# Headers.net
KiCad netlist of a schematic drawn in Altium Designer
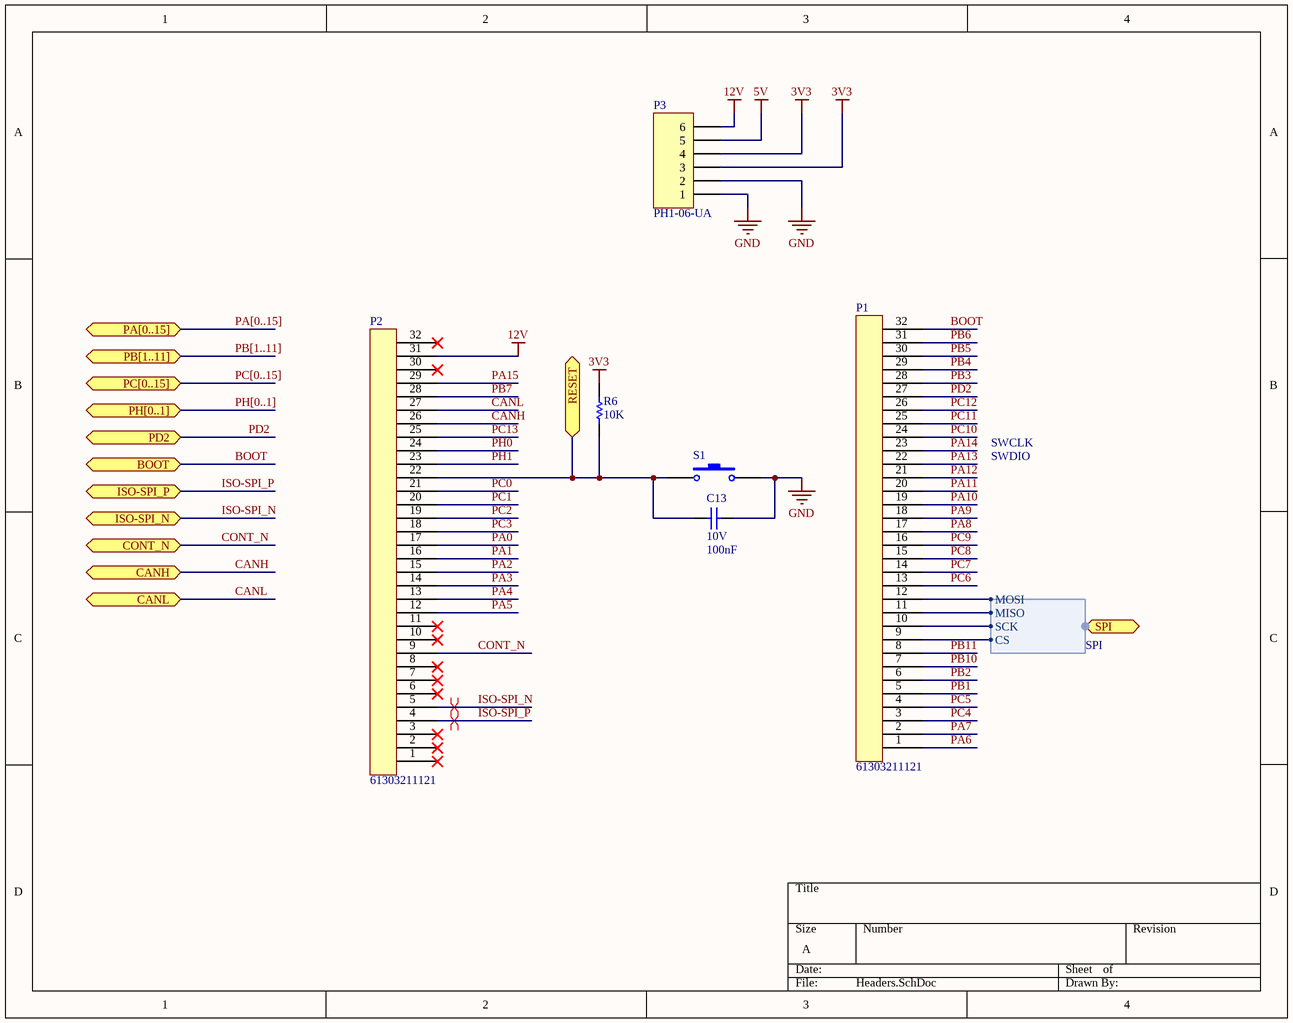
[diagram p0: Headers.SchDoc]

(export (version "E")
  (design (tool "Eeschema 10.0.6"))
  (components
    (comp (ref "C13")
      (value "10V")
      (footprint "C0805")
      (description "C0805C104K8RACTU. 0.1µF ±10% 10V Ceramic Capacitor X7R 0805 (2012 Metric)")
      (fields (field (name "ALTIUM_VALUE") "100nF") (field (name "PUBLISHER") "Altium Limited"))
      (libsource (lib "Miscellaneous Devices") (part "Cap"))
    )
    (comp (ref "P1")
      (value "61303211121")
      (footprint "61303211121")
      (libsource (lib "MCU") (part "61303211121"))
    )
    (comp (ref "P2")
      (value "61303211121")
      (footprint "61303211121")
      (libsource (lib "MCU") (part "61303211121"))
    )
    (comp (ref "P3")
      (value "PH1-06-UA")
      (footprint "PH1-06-UA")
      (description "Connector Header Through Hole 6 position 0.100\" (2.54mm)")
      (fields (field (name "PUBLISHER") "Altium Limited"))
      (libsource (lib "Miscellaneous Connectors") (part "Header 6"))
    )
    (comp (ref "R6")
      (value "10K")
      (footprint "J1-0603")
      (fields (field (name "Comment") "5%") (field (name "PUBLISHER") "Altium Limited"))
      (libsource (lib "Miscellaneous Devices") (part "Res1"))
    )
    (comp (ref "S1")
      (value "PTS636 SM43 SMTR LFS")
      (footprint "PTS636 SM43 SMTR LFS")
      (description "Tactile Switch SPST-NO Top Actuated Surface Mount")
      (fields (field (name "PUBLISHER") "Altium Limited"))
      (libsource (lib "Miscellaneous Devices") (part "SW-PB"))
    )
  )
  (nets
    (net (code "6") (name "/BOOT") (class "Default") (node (ref "P1") (pin "32") (pintype "passive")))
    (net (code "7") (name "/CANH") (class "Default") (node (ref "P2") (pin "26") (pintype "passive")))
    (net (code "8") (name "/CANL") (class "Default") (node (ref "P2") (pin "27") (pintype "passive")))
    (net (code "9") (name "/CONT_N") (class "Default") (node (ref "P2") (pin "9") (pintype "passive")))
    (net (code "10") (name "/CS") (class "Default") (node (ref "P1") (pin "9") (pintype "passive")))
    (net (code "11") (name "/ISO-SPI_N") (class "Default") (node (ref "P2") (pin "5") (pintype "passive")))
    (net (code "12") (name "/ISO-SPI_P") (class "Default") (node (ref "P2") (pin "4") (pintype "passive")))
    (net (code "13") (name "/MISO") (class "Default") (node (ref "P1") (pin "11") (pintype "passive")))
    (net (code "14") (name "/MOSI") (class "Default") (node (ref "P1") (pin "12") (pintype "passive")))
    (net (code "15") (name "/PA0") (class "Default") (node (ref "P2") (pin "17") (pintype "passive")))
    (net (code "16") (name "/PA1") (class "Default") (node (ref "P2") (pin "16") (pintype "passive")))
    (net (code "17") (name "/PA2") (class "Default") (node (ref "P2") (pin "15") (pintype "passive")))
    (net (code "18") (name "/PA3") (class "Default") (node (ref "P2") (pin "14") (pintype "passive")))
    (net (code "19") (name "/PA4") (class "Default") (node (ref "P2") (pin "13") (pintype "passive")))
    (net (code "20") (name "/PA5") (class "Default") (node (ref "P2") (pin "12") (pintype "passive")))
    (net (code "21") (name "/PA6") (class "Default") (node (ref "P1") (pin "1") (pintype "passive")))
    (net (code "22") (name "/PA7") (class "Default") (node (ref "P1") (pin "2") (pintype "passive")))
    (net (code "23") (name "/PA8") (class "Default") (node (ref "P1") (pin "17") (pintype "passive")))
    (net (code "24") (name "/PA9") (class "Default") (node (ref "P1") (pin "18") (pintype "passive")))
    (net (code "25") (name "/PA10") (class "Default") (node (ref "P1") (pin "19") (pintype "passive")))
    (net (code "26") (name "/PA11") (class "Default") (node (ref "P1") (pin "20") (pintype "passive")))
    (net (code "27") (name "/PA12") (class "Default") (node (ref "P1") (pin "21") (pintype "passive")))
    (net (code "28") (name "/PA13") (class "Default") (node (ref "P1") (pin "22") (pintype "passive")))
    (net (code "29") (name "/PA14") (class "Default") (node (ref "P1") (pin "23") (pintype "passive")))
    (net (code "30") (name "/PA15") (class "Default") (node (ref "P2") (pin "29") (pintype "passive")))
    (net (code "32") (name "/PB1") (class "Default") (node (ref "P1") (pin "5") (pintype "passive")))
    (net (code "33") (name "/PB2") (class "Default") (node (ref "P1") (pin "6") (pintype "passive")))
    (net (code "34") (name "/PB3") (class "Default") (node (ref "P1") (pin "28") (pintype "passive")))
    (net (code "35") (name "/PB4") (class "Default") (node (ref "P1") (pin "29") (pintype "passive")))
    (net (code "36") (name "/PB5") (class "Default") (node (ref "P1") (pin "30") (pintype "passive")))
    (net (code "37") (name "/PB6") (class "Default") (node (ref "P1") (pin "31") (pintype "passive")))
    (net (code "38") (name "/PB7") (class "Default") (node (ref "P2") (pin "28") (pintype "passive")))
    (net (code "39") (name "/PB10") (class "Default") (node (ref "P1") (pin "7") (pintype "passive")))
    (net (code "40") (name "/PB11") (class "Default") (node (ref "P1") (pin "8") (pintype "passive")))
    (net (code "42") (name "/PC0") (class "Default") (node (ref "P2") (pin "21") (pintype "passive")))
    (net (code "43") (name "/PC1") (class "Default") (node (ref "P2") (pin "20") (pintype "passive")))
    (net (code "44") (name "/PC2") (class "Default") (node (ref "P2") (pin "19") (pintype "passive")))
    (net (code "45") (name "/PC3") (class "Default") (node (ref "P2") (pin "18") (pintype "passive")))
    (net (code "46") (name "/PC4") (class "Default") (node (ref "P1") (pin "3") (pintype "passive")))
    (net (code "47") (name "/PC5") (class "Default") (node (ref "P1") (pin "4") (pintype "passive")))
    (net (code "48") (name "/PC6") (class "Default") (node (ref "P1") (pin "13") (pintype "passive")))
    (net (code "49") (name "/PC7") (class "Default") (node (ref "P1") (pin "14") (pintype "passive")))
    (net (code "50") (name "/PC8") (class "Default") (node (ref "P1") (pin "15") (pintype "passive")))
    (net (code "51") (name "/PC9") (class "Default") (node (ref "P1") (pin "16") (pintype "passive")))
    (net (code "52") (name "/PC10") (class "Default") (node (ref "P1") (pin "24") (pintype "passive")))
    (net (code "53") (name "/PC11") (class "Default") (node (ref "P1") (pin "25") (pintype "passive")))
    (net (code "54") (name "/PC12") (class "Default") (node (ref "P1") (pin "26") (pintype "passive")))
    (net (code "55") (name "/PC13") (class "Default") (node (ref "P2") (pin "25") (pintype "passive")))
    (net (code "57") (name "/PD2") (class "Default") (node (ref "P1") (pin "27") (pintype "passive")))
    (net (code "58") (name "/PH0") (class "Default") (node (ref "P2") (pin "24") (pintype "passive")))
    (net (code "59") (name "/PH1") (class "Default") (node (ref "P2") (pin "23") (pintype "passive")))
    (net (code "61") (name "/RESET") (class "Default")
      (node (ref "C13") (pin "1") (pinfunction "1_1") (pintype "passive"))
      (node (ref "P2") (pin "22") (pintype "passive"))
      (node (ref "R6") (pin "1") (pinfunction "1_1") (pintype "passive"))
      (node (ref "S1") (pin "1") (pinfunction "1_1") (pintype "passive"))
    )
    (net (code "62") (name "/SCK") (class "Default") (node (ref "P1") (pin "10") (pintype "passive")))
    (net (code "64") (name "3V3") (class "Default")
      (node (ref "P3") (pin "3") (pinfunction "3_3") (pintype "passive"))
      (node (ref "P3") (pin "4") (pinfunction "4_4") (pintype "passive"))
      (node (ref "R6") (pin "2") (pinfunction "2_2") (pintype "passive"))
    )
    (net (code "65") (name "5V") (class "Default")
      (node (ref "P3") (pin "5") (pinfunction "5_5") (pintype "passive"))
    )
    (net (code "66") (name "12V") (class "Default")
      (node (ref "P2") (pin "31") (pintype "passive"))
      (node (ref "P3") (pin "6") (pinfunction "6_6") (pintype "passive"))
    )
    (net (code "67") (name "GND") (class "Default")
      (node (ref "C13") (pin "2") (pinfunction "2_2") (pintype "passive"))
      (node (ref "P3") (pin "1") (pinfunction "1_1") (pintype "passive"))
      (node (ref "P3") (pin "2") (pinfunction "2_2") (pintype "passive"))
      (node (ref "S1") (pin "2") (pinfunction "2_2") (pintype "passive"))
    )
    (net (code "68") (name "unconnected-(P2-Pad1)") (class "Default")
      (node (ref "P2") (pin "1") (pintype "passive+no_connect"))
    )
    (net (code "69") (name "unconnected-(P2-Pad2)") (class "Default")
      (node (ref "P2") (pin "2") (pintype "passive+no_connect"))
    )
    (net (code "70") (name "unconnected-(P2-Pad3)") (class "Default")
      (node (ref "P2") (pin "3") (pintype "passive+no_connect"))
    )
    (net (code "71") (name "unconnected-(P2-Pad6)") (class "Default")
      (node (ref "P2") (pin "6") (pintype "passive+no_connect"))
    )
    (net (code "72") (name "unconnected-(P2-Pad7)") (class "Default")
      (node (ref "P2") (pin "7") (pintype "passive+no_connect"))
    )
    (net (code "73") (name "unconnected-(P2-Pad8)") (class "Default")
      (node (ref "P2") (pin "8") (pintype "passive+no_connect"))
    )
    (net (code "74") (name "unconnected-(P2-Pad10)") (class "Default")
      (node (ref "P2") (pin "10") (pintype "passive+no_connect"))
    )
    (net (code "75") (name "unconnected-(P2-Pad11)") (class "Default")
      (node (ref "P2") (pin "11") (pintype "passive+no_connect"))
    )
    (net (code "76") (name "unconnected-(P2-Pad30)") (class "Default")
      (node (ref "P2") (pin "30") (pintype "passive+no_connect"))
    )
    (net (code "77") (name "unconnected-(P2-Pad32)") (class "Default")
      (node (ref "P2") (pin "32") (pintype "passive+no_connect"))
    )
  )
)
